# concentrador.net
KiCad netlist of a schematic drawn in Altium Designer
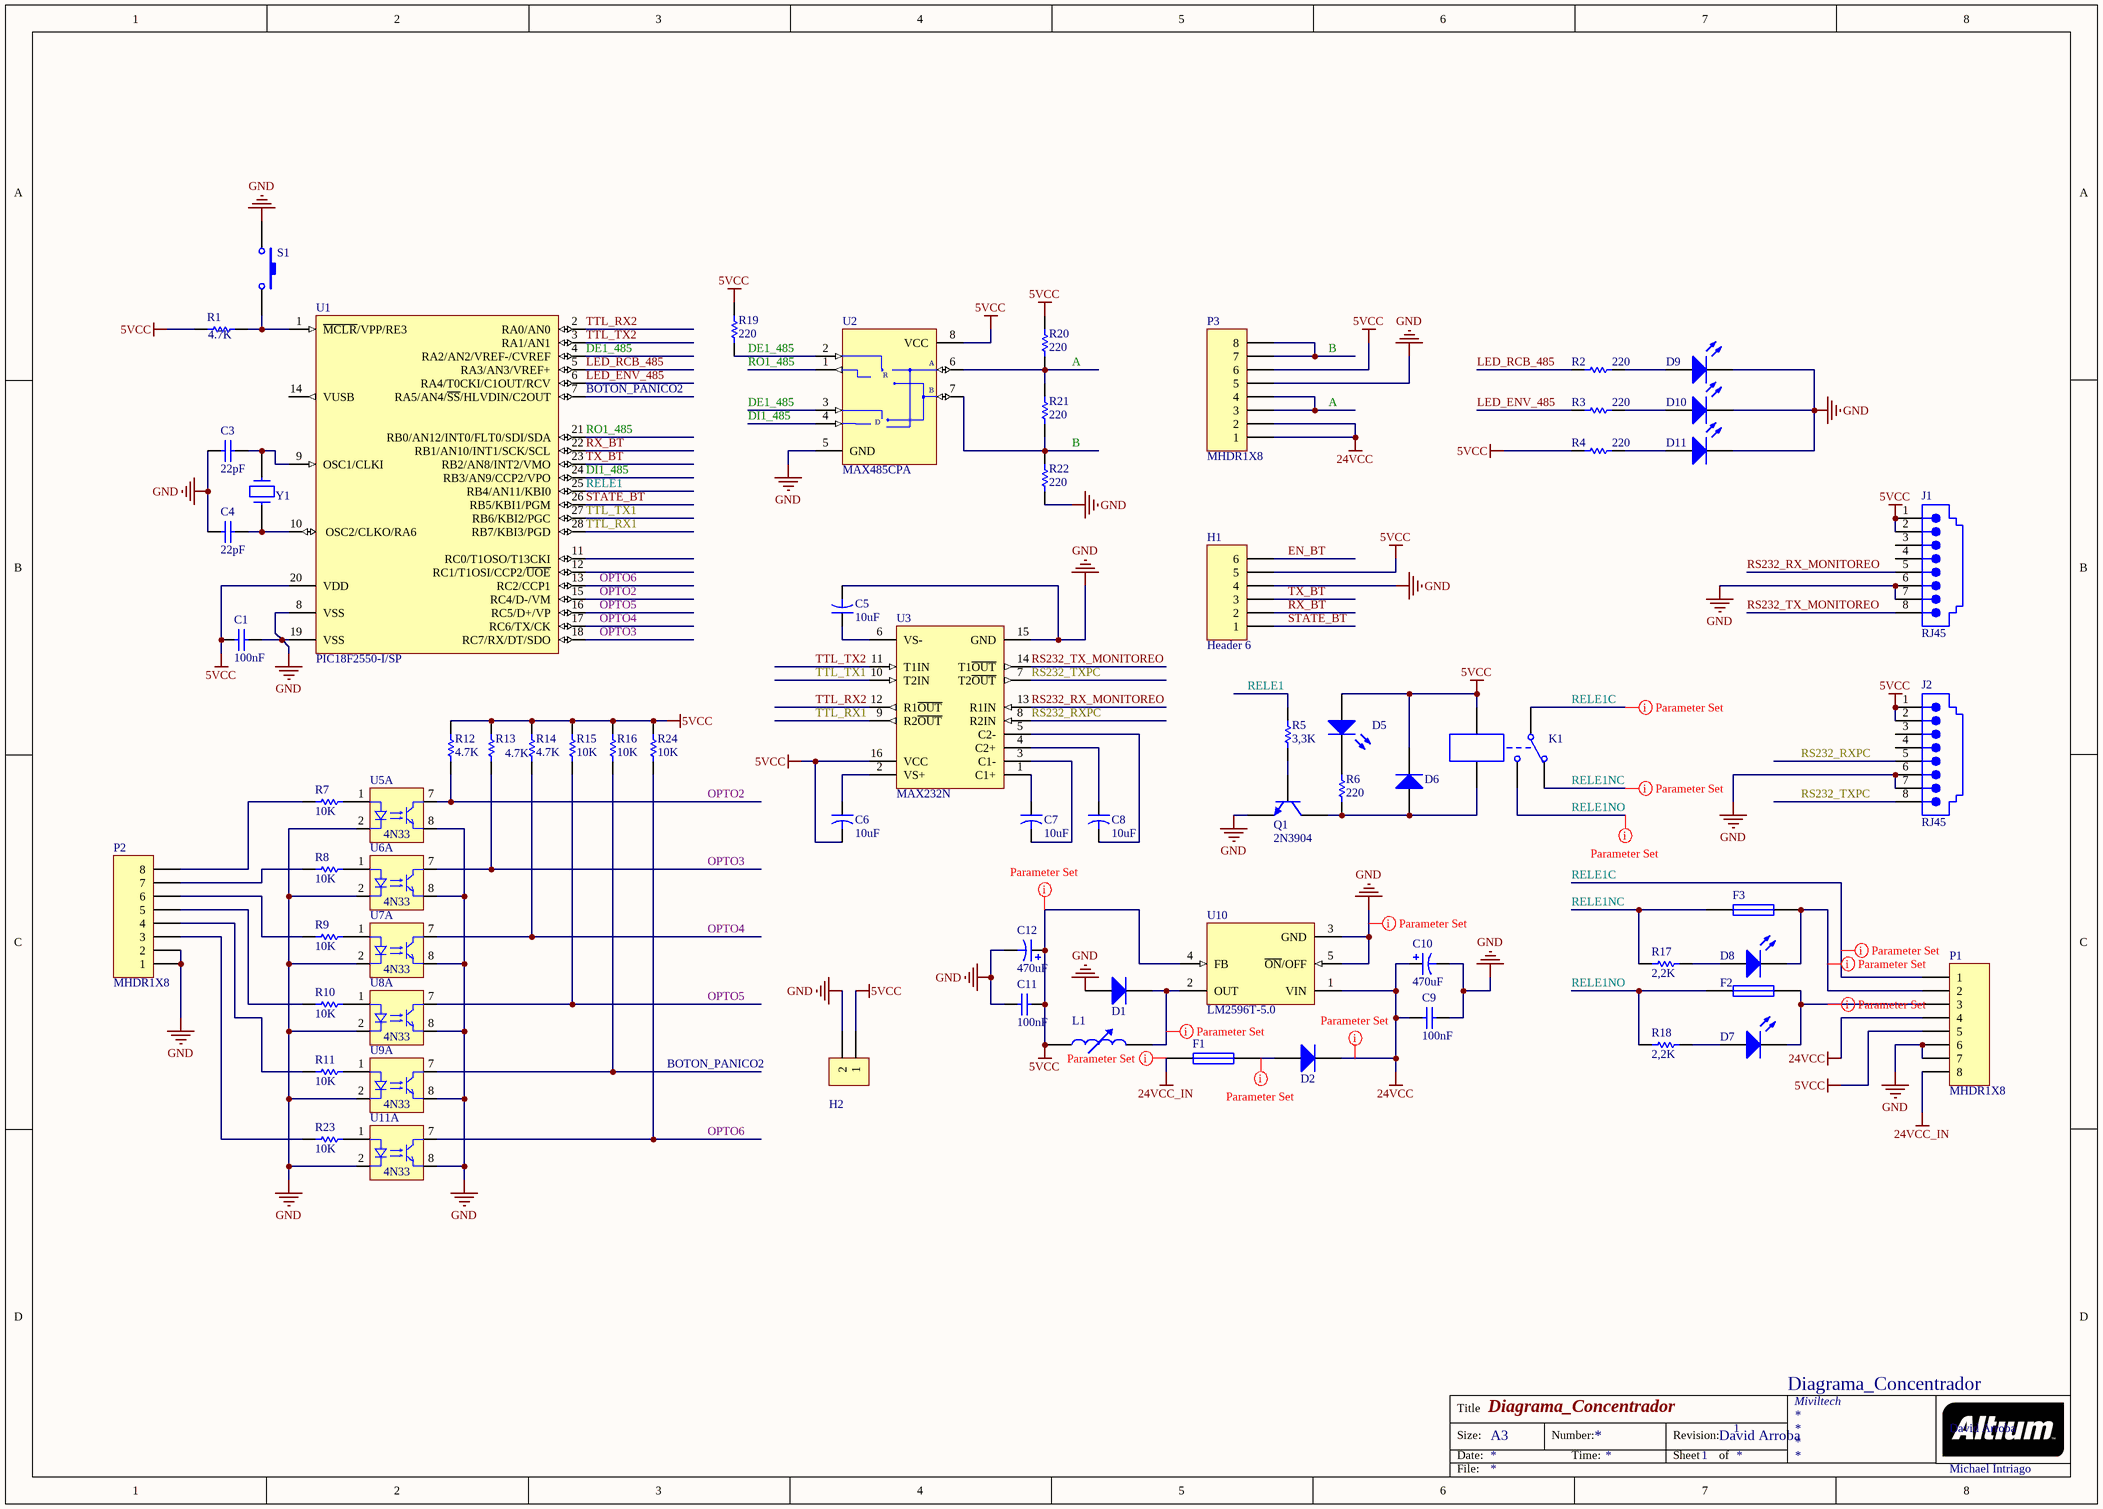
[diagram p0: concentrador.SchDoc]

(export (version "E")
  (design (tool "Eeschema 10.0.6"))
  (components
    (comp (ref "C1")
      (value "100nF")
      (footprint "VP44-2.5")
      (description "Dipped Radial Multilayer Ceramic Capacitor X7R: 220nF, 100V")
      (fields (field (name "Comment") "VP44BY224JB") (field (name "PUBLISHER") "Altium Limited"))
      (libsource (lib "Vishay Vitramon Ceramic Dipped Capacitor") (part "VP44BY224JB"))
    )
    (comp (ref "C3")
      (value "22pF")
      (footprint "VP31-2.5")
      (description "Dipped Radial Multilayer Ceramic Capacitor COG (NPO): 22pF, 100V")
      (fields (field (name "Comment") "VP31BA220JB") (field (name "PUBLISHER") "Altium Limited"))
      (libsource (lib "Vishay Vitramon Ceramic Dipped Capacitor") (part "VP31BA220JB"))
    )
    (comp (ref "C4")
      (value "22pF")
      (footprint "VP31-2.5")
      (description "Dipped Radial Multilayer Ceramic Capacitor COG (NPO): 22pF, 100V")
      (fields (field (name "Comment") "VP31BA220JB") (field (name "PUBLISHER") "Altium Limited"))
      (libsource (lib "Vishay Vitramon Ceramic Dipped Capacitor") (part "VP31BA220JB"))
    )
    (comp (ref "C5")
      (value "10uF")
      (footprint "C1UF")
      (description "Capacitor")
      (fields (field (name "Comment") "Cap2") (field (name "PUBLISHER") "Altium Limited"))
      (libsource (lib "Miscellaneous Devices") (part "Cap2"))
    )
    (comp (ref "C6")
      (value "10uF")
      (footprint "C1UF")
      (description "Capacitor")
      (fields (field (name "Comment") "Cap2") (field (name "PUBLISHER") "Altium Limited"))
      (libsource (lib "Miscellaneous Devices") (part "Cap2"))
    )
    (comp (ref "C7")
      (value "10uF")
      (footprint "C1UF")
      (description "Capacitor")
      (fields (field (name "Comment") "Cap2") (field (name "PUBLISHER") "Altium Limited"))
      (libsource (lib "Miscellaneous Devices") (part "Cap2"))
    )
    (comp (ref "C8")
      (value "10uF")
      (footprint "C1UF")
      (description "Capacitor")
      (fields (field (name "Comment") "Cap2") (field (name "PUBLISHER") "Altium Limited"))
      (libsource (lib "Miscellaneous Devices") (part "Cap2"))
    )
    (comp (ref "C9")
      (value "100nF")
      (footprint "VP44-2.5")
      (description "Dipped Radial Multilayer Ceramic Capacitor X7R: 220nF, 100V")
      (fields (field (name "Comment") "VP44BY224JB") (field (name "PUBLISHER") "Altium Limited"))
      (libsource (lib "Vishay Vitramon Ceramic Dipped Capacitor") (part "VP44BY224JB"))
    )
    (comp (ref "C10")
      (value "470uF")
      (footprint "C1000UF")
      (description "Polarized Capacitor (Radial)")
      (fields (field (name "Comment") "Cap Pol1") (field (name "PUBLISHER") "Altium Limited"))
      (libsource (lib "Miscellaneous Devices") (part "Cap Pol1"))
    )
    (comp (ref "C11")
      (value "100nF")
      (footprint "VP44-2.5")
      (description "Dipped Radial Multilayer Ceramic Capacitor X7R: 220nF, 100V")
      (fields (field (name "Comment") "VP44BY224JB") (field (name "PUBLISHER") "Altium Limited"))
      (libsource (lib "Vishay Vitramon Ceramic Dipped Capacitor") (part "VP44BY224JB"))
    )
    (comp (ref "C12")
      (value "470uF")
      (footprint "C1000UF")
      (description "Polarized Capacitor (Radial)")
      (fields (field (name "Comment") "Cap Pol1") (field (name "PUBLISHER") "Altium Limited"))
      (libsource (lib "Miscellaneous Devices") (part "Cap Pol1"))
    )
    (comp (ref "D1")
      (value "Diodo")
      (footprint "1N4000")
      (description "Diodo rectificador")
      (libsource (lib "Diodos") (part "Diodo"))
    )
    (comp (ref "D2")
      (value "Diodo")
      (footprint "1N4000")
      (description "Diodo rectificador")
      (libsource (lib "Diodos") (part "Diodo"))
    )
    (comp (ref "D5")
      (value "LED0")
      (footprint "LED3MM green")
      (description "Typical INFRARED GaAs LED")
      (fields (field (name "PUBLISHER") "Altium Limited"))
      (libsource (lib "Miscellaneous Devices") (part "LED0"))
    )
    (comp (ref "D6")
      (value "Diode 1N4001")
      (footprint "DIODE-0.3A")
      (description "1 Amp General Purpose Rectifier")
      (fields (field (name "PUBLISHER") "Altium Limited"))
      (libsource (lib "Miscellaneous Devices") (part "Diode 1N4001"))
    )
    (comp (ref "D7")
      (value "LED0")
      (footprint "LED3MM green")
      (description "Typical INFRARED GaAs LED")
      (fields (field (name "PUBLISHER") "Altium Limited"))
      (libsource (lib "Miscellaneous Devices") (part "LED0"))
    )
    (comp (ref "D8")
      (value "LED0")
      (footprint "LED3MM green")
      (description "Typical INFRARED GaAs LED")
      (fields (field (name "PUBLISHER") "Altium Limited"))
      (libsource (lib "Miscellaneous Devices") (part "LED0"))
    )
    (comp (ref "D9")
      (value "LED0")
      (footprint "LED3MM green")
      (description "Typical INFRARED GaAs LED")
      (fields (field (name "PUBLISHER") "Altium Limited"))
      (libsource (lib "Miscellaneous Devices") (part "LED0"))
    )
    (comp (ref "D10")
      (value "LED0")
      (footprint "LED3MM green")
      (description "Typical INFRARED GaAs LED")
      (fields (field (name "PUBLISHER") "Altium Limited"))
      (libsource (lib "Miscellaneous Devices") (part "LED0"))
    )
    (comp (ref "D11")
      (value "LED0")
      (footprint "LED3MM green")
      (description "Typical INFRARED GaAs LED")
      (fields (field (name "PUBLISHER") "Altium Limited"))
      (libsource (lib "Miscellaneous Devices") (part "LED0"))
    )
    (comp (ref "F1")
      (value "Fuse")
      (footprint "PORTA_FUSE")
      (fields (field (name "PUBLISHER") "Altium Limited"))
      (libsource (lib "Miscellaneous Devices") (part "Fuse 1"))
    )
    (comp (ref "F2")
      (value "Fuse")
      (footprint "PORTA_FUSE")
      (fields (field (name "PUBLISHER") "Altium Limited"))
      (libsource (lib "Miscellaneous Devices") (part "Fuse 1"))
    )
    (comp (ref "F3")
      (value "Fuse")
      (footprint "PORTA_FUSE")
      (fields (field (name "PUBLISHER") "Altium Limited"))
      (libsource (lib "Miscellaneous Devices") (part "Fuse 1"))
    )
    (comp (ref "H1")
      (value "Header 6")
      (footprint "Header 1X6")
      (description "Header, 6-Pin")
      (fields (field (name "PUBLISHER") "Altium Limited"))
      (libsource (lib "Conectores") (part "Header 6"))
    )
    (comp (ref "H2")
      (value "Header")
      (footprint "Header 1X2")
      (description "Header 2 pin")
      (libsource (lib "Conectores") (part "Header 2"))
    )
    (comp (ref "J1")
      (value "RJ45")
      (footprint "15-43-6233")
      (description "Right Angle, Standard Profile, RJ45-Keyed, Flange Mount PCB Jack")
      (fields (field (name "PUBLISHER") "Altium Limited"))
      (libsource (lib "Molex Modular Jack Right Angle") (part "15-43-6233"))
    )
    (comp (ref "J2")
      (value "RJ45")
      (footprint "15-43-6233")
      (description "Right Angle, Standard Profile, RJ45-Keyed, Flange Mount PCB Jack")
      (fields (field (name "PUBLISHER") "Altium Limited"))
      (libsource (lib "Molex Modular Jack Right Angle") (part "15-43-6233"))
    )
    (comp (ref "K1")
      (value "Relay-SPDT")
      (footprint "RELE")
      (description "Single-Pole Dual-Throw Relay")
      (fields (field (name "PUBLISHER") "Altium Limited"))
      (libsource (lib "Miscellaneous Devices") (part "Relay-SPDT"))
    )
    (comp (ref "L1")
      (value "Inductor Adj")
      (footprint "Inductor_redondo")
      (description "Adjustable Inductor")
      (fields (field (name "PUBLISHER") "Altium Limited"))
      (libsource (lib "Miscellaneous Devices") (part "Inductor Adj"))
    )
    (comp (ref "P1")
      (value "MHDR1X8")
      (footprint "8PEQ_TAIYUE_OK")
      (description "Header, 8-Pin")
      (fields (field (name "PUBLISHER") "Altium Limited"))
      (libsource (lib "") (part "MHDR1X8_1"))
    )
    (comp (ref "P2")
      (value "MHDR1X8")
      (footprint "8PEQ_TAIYUE_OK")
      (description "Header, 8-Pin")
      (fields (field (name "PUBLISHER") "Altium Limited"))
      (libsource (lib "Miscellaneous Connectors") (part "MHDR1X8"))
    )
    (comp (ref "P3")
      (value "MHDR1X8")
      (footprint "8PEQ_TAIYUE_OK")
      (description "Header, 8-Pin")
      (fields (field (name "PUBLISHER") "Altium Limited"))
      (libsource (lib "Miscellaneous Connectors") (part "MHDR1X8"))
    )
    (comp (ref "Q1")
      (value "2N3904")
      (footprint "2N3904_OK")
      (description "NPN General Purpose Amplifier")
      (fields (field (name "PUBLISHER") "Altium Limited"))
      (libsource (lib "Miscellaneous Devices") (part "2N3904"))
    )
    (comp (ref "R1")
      (value "4.7K")
      (footprint "AXIAL-0.3")
      (description "Resistor")
      (fields (field (name "Comment") "Res1") (field (name "PUBLISHER") "Altium Limited"))
      (libsource (lib "Miscellaneous Devices") (part "Res1"))
    )
    (comp (ref "R2")
      (value "220")
      (footprint "AXIAL-0.3")
      (description "Resistor")
      (fields (field (name "Comment") "Res1") (field (name "PUBLISHER") "Altium Limited"))
      (libsource (lib "Miscellaneous Devices") (part "Res1"))
    )
    (comp (ref "R3")
      (value "220")
      (footprint "AXIAL-0.3")
      (description "Resistor")
      (fields (field (name "Comment") "Res1") (field (name "PUBLISHER") "Altium Limited"))
      (libsource (lib "Miscellaneous Devices") (part "Res1"))
    )
    (comp (ref "R4")
      (value "220")
      (footprint "AXIAL-0.3")
      (description "Resistor")
      (fields (field (name "Comment") "Res1") (field (name "PUBLISHER") "Altium Limited"))
      (libsource (lib "Miscellaneous Devices") (part "Res1"))
    )
    (comp (ref "R5")
      (value "3,3K")
      (footprint "AXIAL-0.3")
      (description "Resistor")
      (fields (field (name "Comment") "Res1") (field (name "PUBLISHER") "Altium Limited"))
      (libsource (lib "Miscellaneous Devices") (part "Res1"))
    )
    (comp (ref "R6")
      (value "220")
      (footprint "AXIAL-0.3")
      (description "Resistor")
      (fields (field (name "Comment") "Res1") (field (name "PUBLISHER") "Altium Limited"))
      (libsource (lib "Miscellaneous Devices") (part "Res1"))
    )
    (comp (ref "R7")
      (value "10K")
      (footprint "AXIAL-0.3")
      (description "Resistor")
      (fields (field (name "Comment") "Res1") (field (name "PUBLISHER") "Altium Limited"))
      (libsource (lib "Miscellaneous Devices") (part "Res1"))
    )
    (comp (ref "R8")
      (value "10K")
      (footprint "AXIAL-0.3")
      (description "Resistor")
      (fields (field (name "Comment") "Res1") (field (name "PUBLISHER") "Altium Limited"))
      (libsource (lib "Miscellaneous Devices") (part "Res1"))
    )
    (comp (ref "R9")
      (value "10K")
      (footprint "AXIAL-0.3")
      (description "Resistor")
      (fields (field (name "Comment") "Res1") (field (name "PUBLISHER") "Altium Limited"))
      (libsource (lib "Miscellaneous Devices") (part "Res1"))
    )
    (comp (ref "R10")
      (value "10K")
      (footprint "AXIAL-0.3")
      (description "Resistor")
      (fields (field (name "Comment") "Res1") (field (name "PUBLISHER") "Altium Limited"))
      (libsource (lib "Miscellaneous Devices") (part "Res1"))
    )
    (comp (ref "R11")
      (value "10K")
      (footprint "AXIAL-0.3")
      (description "Resistor")
      (fields (field (name "Comment") "Res1") (field (name "PUBLISHER") "Altium Limited"))
      (libsource (lib "Miscellaneous Devices") (part "Res1"))
    )
    (comp (ref "R12")
      (value "4.7K")
      (footprint "AXIAL-0.3")
      (description "Resistor")
      (fields (field (name "Comment") "Res1") (field (name "PUBLISHER") "Altium Limited"))
      (libsource (lib "Miscellaneous Devices") (part "Res1"))
    )
    (comp (ref "R13")
      (value "4.7K")
      (footprint "AXIAL-0.3")
      (description "Resistor")
      (fields (field (name "Comment") "Res1") (field (name "PUBLISHER") "Altium Limited"))
      (libsource (lib "Miscellaneous Devices") (part "Res1"))
    )
    (comp (ref "R14")
      (value "4.7K")
      (footprint "AXIAL-0.3")
      (description "Resistor")
      (fields (field (name "Comment") "Res1") (field (name "PUBLISHER") "Altium Limited"))
      (libsource (lib "Miscellaneous Devices") (part "Res1"))
    )
    (comp (ref "R15")
      (value "10K")
      (footprint "AXIAL-0.3")
      (description "Resistor")
      (fields (field (name "Comment") "Res1") (field (name "PUBLISHER") "Altium Limited"))
      (libsource (lib "Miscellaneous Devices") (part "Res1"))
    )
    (comp (ref "R16")
      (value "10K")
      (footprint "AXIAL-0.3")
      (description "Resistor")
      (fields (field (name "Comment") "Res1") (field (name "PUBLISHER") "Altium Limited"))
      (libsource (lib "Miscellaneous Devices") (part "Res1"))
    )
    (comp (ref "R17")
      (value "2,2K")
      (footprint "AXIAL-0.3")
      (description "Resistor")
      (fields (field (name "Comment") "Res1") (field (name "PUBLISHER") "Altium Limited"))
      (libsource (lib "Miscellaneous Devices") (part "Res1"))
    )
    (comp (ref "R18")
      (value "2,2K")
      (footprint "AXIAL-0.3")
      (description "Resistor")
      (fields (field (name "Comment") "Res1") (field (name "PUBLISHER") "Altium Limited"))
      (libsource (lib "Miscellaneous Devices") (part "Res1"))
    )
    (comp (ref "R19")
      (value "220")
      (footprint "AXIAL-0.3")
      (description "Resistor")
      (fields (field (name "Comment") "Res1") (field (name "PUBLISHER") "Altium Limited"))
      (libsource (lib "Miscellaneous Devices") (part "Res1"))
    )
    (comp (ref "R20")
      (value "220")
      (footprint "AXIAL-0.3")
      (description "Resistor")
      (fields (field (name "Comment") "Res1") (field (name "PUBLISHER") "Altium Limited"))
      (libsource (lib "Miscellaneous Devices") (part "Res1"))
    )
    (comp (ref "R21")
      (value "220")
      (footprint "AXIAL-0.3")
      (description "Resistor")
      (fields (field (name "Comment") "Res1") (field (name "PUBLISHER") "Altium Limited"))
      (libsource (lib "Miscellaneous Devices") (part "Res1"))
    )
    (comp (ref "R22")
      (value "220")
      (footprint "AXIAL-0.3")
      (description "Resistor")
      (fields (field (name "Comment") "Res1") (field (name "PUBLISHER") "Altium Limited"))
      (libsource (lib "Miscellaneous Devices") (part "Res1"))
    )
    (comp (ref "R23")
      (value "10K")
      (footprint "AXIAL-0.3")
      (description "Resistor")
      (fields (field (name "Comment") "Res1") (field (name "PUBLISHER") "Altium Limited"))
      (libsource (lib "Miscellaneous Devices") (part "Res1"))
    )
    (comp (ref "R24")
      (value "10K")
      (footprint "AXIAL-0.3")
      (description "Resistor")
      (fields (field (name "Comment") "Res1") (field (name "PUBLISHER") "Altium Limited"))
      (libsource (lib "Miscellaneous Devices") (part "Res1"))
    )
    (comp (ref "S1")
      (value "Push Button")
      (footprint "PULSA4")
      (description "Switch")
      (fields (field (name "PUBLISHER") "Altium Limited"))
      (libsource (lib "Botones") (part "Push Button"))
    )
    (comp (ref "U1")
      (value "PIC18F2550-I/SP")
      (footprint "SPDIP300-SP28")
      (fields (field (name "PUBLISHER") "Altium Limited"))
      (libsource (lib "Microchip Microcontroller 8-Bit PIC18") (part "PIC18F2550-I/SP"))
    )
    (comp (ref "U2")
      (value "MAX485CPA")
      (footprint "PA8")
      (description "Low-Power, Slew-Rate-Limited RS-485/RS-422 Transceiver")
      (fields (field (name "PUBLISHER") "Altium Limited"))
      (libsource (lib "Maxim Communication Transceiver") (part "MAX485CPA"))
    )
    (comp (ref "U3")
      (value "MAX232N")
      (footprint "N016")
      (description "Dual EIA-232 Driver/Receiver")
      (fields (field (name "PUBLISHER") "Altium Limited"))
      (libsource (lib "TI Interface Line Transceiver") (part "MAX232N"))
    )
    (comp (ref "U5")
      (value "4N33")
      (footprint "4n35_4n33_6pines")
      (description "Optocoupler, Phototransistor Output, Dual Channel, TTL Compatible, Pb-free")
      (fields (field (name "PUBLISHER") "Altium Limited"))
      (libsource (lib "Vishay Optoelectronic Optocoupler") (part "ILD74"))
    )
    (comp (ref "U6")
      (value "4N33")
      (footprint "4n35_4n33_6pines")
      (description "Optocoupler, Phototransistor Output, Dual Channel, TTL Compatible, Pb-free")
      (fields (field (name "PUBLISHER") "Altium Limited"))
      (libsource (lib "Vishay Optoelectronic Optocoupler") (part "ILD74"))
    )
    (comp (ref "U7")
      (value "4N33")
      (footprint "4n35_4n33_6pines")
      (description "Optocoupler, Phototransistor Output, Dual Channel, TTL Compatible, Pb-free")
      (fields (field (name "PUBLISHER") "Altium Limited"))
      (libsource (lib "Vishay Optoelectronic Optocoupler") (part "ILD74"))
    )
    (comp (ref "U8")
      (value "4N33")
      (footprint "4n35_4n33_6pines")
      (description "Optocoupler, Phototransistor Output, Dual Channel, TTL Compatible, Pb-free")
      (fields (field (name "PUBLISHER") "Altium Limited"))
      (libsource (lib "Vishay Optoelectronic Optocoupler") (part "ILD74"))
    )
    (comp (ref "U9")
      (value "4N33")
      (footprint "4n35_4n33_6pines")
      (description "Optocoupler, Phototransistor Output, Dual Channel, TTL Compatible, Pb-free")
      (fields (field (name "PUBLISHER") "Altium Limited"))
      (libsource (lib "Vishay Optoelectronic Optocoupler") (part "ILD74"))
    )
    (comp (ref "U10")
      (value "LM2596T-5.0")
      (footprint "FP_LM2596_D_PCB")
      (description "SIMPLE SWITCHER Power Converter 150 KHz 3A Step-Down Voltage Regulator")
      (fields
        (field (name "MANUFACTURER") "National Semiconductor")
        (field (name "DIGIKEYPARTNUMBER") "LM2596T-5.0-ND")
        (field (name "PUBLISHER") "Altium Limited")
      )
      (libsource (lib "NSC Switcher") (part "LM2596T-5.0"))
    )
    (comp (ref "U11")
      (value "4N33")
      (footprint "4n35_4n33_6pines")
      (description "Optocoupler, Phototransistor Output, Dual Channel, TTL Compatible, Pb-free")
      (fields (field (name "PUBLISHER") "Altium Limited"))
      (libsource (lib "Vishay Optoelectronic Optocoupler") (part "ILD74"))
    )
    (comp (ref "Y1")
      (value "XTAL")
      (footprint "Cristal mini")
      (description "Cristal de cuarzo")
      (libsource (lib "Cristales de cuarzo") (part "Cristal de cuarzo"))
    )
  )
  (nets
    (net (code "1") (name "/A") (class "Default")
      (node (ref "P3") (pin "3") (pinfunction "3_3") (pintype "passive"))
      (node (ref "P3") (pin "4") (pinfunction "4_4") (pintype "passive"))
      (node (ref "R20") (pin "2") (pinfunction "2_2") (pintype "passive"))
      (node (ref "R21") (pin "1") (pinfunction "1_1") (pintype "passive"))
      (node (ref "U2") (pin "6") (pinfunction "A_6") (pintype "bidirectional"))
    )
    (net (code "2") (name "/B") (class "Default")
      (node (ref "P3") (pin "7") (pinfunction "7_7") (pintype "passive"))
      (node (ref "P3") (pin "8") (pinfunction "8_8") (pintype "passive"))
      (node (ref "R21") (pin "2") (pinfunction "2_2") (pintype "passive"))
      (node (ref "R22") (pin "1") (pinfunction "1_1") (pintype "passive"))
      (node (ref "U2") (pin "7") (pinfunction "B_7") (pintype "bidirectional"))
    )
    (net (code "3") (name "/BOTON_PANICO2") (class "Default")
      (node (ref "R16") (pin "2") (pinfunction "2_2") (pintype "passive"))
      (node (ref "U1") (pin "7") (pinfunction "RA5/AN4/~{SS}/HLVDIN/C2OUT_7") (pintype "bidirectional"))
      (node (ref "U9") (pin "7") (pinfunction "C_7") (pintype "passive"))
    )
    (net (code "4") (name "/DE1_485") (class "Default")
      (node (ref "R19") (pin "1") (pinfunction "1_1") (pintype "passive"))
      (node (ref "U1") (pin "4") (pinfunction "RA2/AN2/VREF-/CVREF_4") (pintype "bidirectional"))
      (node (ref "U2") (pin "2") (pinfunction "~{RE}_2") (pintype "input"))
      (node (ref "U2") (pin "3") (pinfunction "DE_3") (pintype "input"))
    )
    (net (code "5") (name "/DI1_485") (class "Default")
      (node (ref "U1") (pin "24") (pinfunction "RB3/AN9/CCP2/VPO_24") (pintype "bidirectional"))
      (node (ref "U2") (pin "4") (pinfunction "DI_4") (pintype "input"))
    )
    (net (code "6") (name "/EN_BT") (class "Default")
      (node (ref "H1") (pin "6") (pinfunction "6_6") (pintype "passive"))
    )
    (net (code "7") (name "/LED_ENV_485") (class "Default")
      (node (ref "R3") (pin "1") (pinfunction "1_1") (pintype "passive"))
      (node (ref "U1") (pin "6") (pinfunction "RA4/T0CKI/C1OUT/RCV_6") (pintype "bidirectional"))
    )
    (net (code "8") (name "/LED_RCB_485") (class "Default")
      (node (ref "R2") (pin "1") (pinfunction "1_1") (pintype "passive"))
      (node (ref "U1") (pin "5") (pinfunction "RA3/AN3/VREF+_5") (pintype "bidirectional"))
    )
    (net (code "9") (name "/OPTO2") (class "Default")
      (node (ref "R12") (pin "2") (pinfunction "2_2") (pintype "passive"))
      (node (ref "U1") (pin "15") (pinfunction "RC4/D-/VM_15") (pintype "bidirectional"))
      (node (ref "U5") (pin "7") (pinfunction "C_7") (pintype "passive"))
    )
    (net (code "10") (name "/OPTO3") (class "Default")
      (node (ref "R13") (pin "2") (pinfunction "2_2") (pintype "passive"))
      (node (ref "U1") (pin "18") (pinfunction "RC7/RX/DT/SDO_18") (pintype "bidirectional"))
      (node (ref "U6") (pin "7") (pinfunction "C_7") (pintype "passive"))
    )
    (net (code "11") (name "/OPTO4") (class "Default")
      (node (ref "R14") (pin "2") (pinfunction "2_2") (pintype "passive"))
      (node (ref "U1") (pin "17") (pinfunction "RC6/TX/CK_17") (pintype "bidirectional"))
      (node (ref "U7") (pin "7") (pinfunction "C_7") (pintype "passive"))
    )
    (net (code "12") (name "/OPTO5") (class "Default")
      (node (ref "R15") (pin "2") (pinfunction "2_2") (pintype "passive"))
      (node (ref "U1") (pin "16") (pinfunction "RC5/D+/VP_16") (pintype "bidirectional"))
      (node (ref "U8") (pin "7") (pinfunction "C_7") (pintype "passive"))
    )
    (net (code "13") (name "/OPTO6") (class "Default")
      (node (ref "R24") (pin "2") (pinfunction "2_2") (pintype "passive"))
      (node (ref "U1") (pin "13") (pinfunction "RC2/CCP1_13") (pintype "bidirectional"))
      (node (ref "U11") (pin "7") (pinfunction "C_7") (pintype "passive"))
    )
    (net (code "14") (name "/RELE1") (class "Default")
      (node (ref "R5") (pin "1") (pinfunction "1_1") (pintype "passive"))
      (node (ref "U1") (pin "25") (pinfunction "RB4/AN11/KBI0_25") (pintype "bidirectional"))
    )
    (net (code "15") (name "/RELE1C") (class "Default")
      (node (ref "K1") (pin "1") (pinfunction "1_1") (pintype "passive"))
      (node (ref "P1") (pin "1") (pinfunction "1_1") (pintype "passive"))
    )
    (net (code "16") (name "/RELE1NC") (class "Default")
      (node (ref "F3") (pin "1") (pinfunction "1_1") (pintype "passive"))
      (node (ref "K1") (pin "2") (pinfunction "2_2") (pintype "passive"))
      (node (ref "R17") (pin "1") (pinfunction "1_1") (pintype "passive"))
    )
    (net (code "17") (name "/RELE1NO") (class "Default")
      (node (ref "F2") (pin "1") (pinfunction "1_1") (pintype "passive"))
      (node (ref "K1") (pin "3") (pinfunction "3_3") (pintype "passive"))
      (node (ref "R18") (pin "1") (pinfunction "1_1") (pintype "passive"))
    )
    (net (code "18") (name "/RO1_485") (class "Default")
      (node (ref "U1") (pin "21") (pinfunction "RB0/AN12/INT0/FLT0/SDI/SDA_21") (pintype "bidirectional"))
      (node (ref "U2") (pin "1") (pinfunction "RO_1") (pintype "output"))
    )
    (net (code "19") (name "/RS232_RXPC") (class "Default")
      (node (ref "J2") (pin "5") (pinfunction "5_5") (pintype "passive"))
      (node (ref "U3") (pin "8") (pinfunction "R2IN_8") (pintype "input"))
    )
    (net (code "20") (name "/RS232_RX_MONITOREO") (class "Default")
      (node (ref "J1") (pin "5") (pinfunction "5_5") (pintype "passive"))
      (node (ref "U3") (pin "13") (pinfunction "R1IN_13") (pintype "input"))
    )
    (net (code "21") (name "/RS232_TXPC") (class "Default")
      (node (ref "J2") (pin "8") (pinfunction "8_8") (pintype "passive"))
      (node (ref "U3") (pin "7") (pinfunction "T2~{OUT}_7") (pintype "output"))
    )
    (net (code "22") (name "/RS232_TX_MONITOREO") (class "Default")
      (node (ref "J1") (pin "8") (pinfunction "8_8") (pintype "passive"))
      (node (ref "U3") (pin "14") (pinfunction "T1~{OUT}_14") (pintype "output"))
    )
    (net (code "23") (name "/RX_BT") (class "Default")
      (node (ref "H1") (pin "2") (pinfunction "2_2") (pintype "passive"))
      (node (ref "U1") (pin "22") (pinfunction "RB1/AN10/INT1/SCK/SCL_22") (pintype "bidirectional"))
    )
    (net (code "24") (name "/STATE_BT") (class "Default")
      (node (ref "H1") (pin "1") (pinfunction "1_1") (pintype "passive"))
      (node (ref "U1") (pin "26") (pinfunction "RB5/KBI1/PGM_26") (pintype "bidirectional"))
    )
    (net (code "25") (name "/TTL_RX1") (class "Default")
      (node (ref "U1") (pin "28") (pinfunction "RB7/KBI3/PGD_28") (pintype "bidirectional"))
      (node (ref "U3") (pin "9") (pinfunction "R2~{OUT}_9") (pintype "output"))
    )
    (net (code "26") (name "/TTL_RX2") (class "Default")
      (node (ref "U1") (pin "2") (pinfunction "RA0/AN0_2") (pintype "bidirectional"))
      (node (ref "U3") (pin "12") (pinfunction "R1~{OUT}_12") (pintype "output"))
    )
    (net (code "27") (name "/TTL_TX1") (class "Default")
      (node (ref "U1") (pin "27") (pinfunction "RB6/KBI2/PGC_27") (pintype "bidirectional"))
      (node (ref "U3") (pin "10") (pinfunction "T2IN_10") (pintype "input"))
    )
    (net (code "28") (name "/TTL_TX2") (class "Default")
      (node (ref "U1") (pin "3") (pinfunction "RA1/AN1_3") (pintype "bidirectional"))
      (node (ref "U3") (pin "11") (pinfunction "T1IN_11") (pintype "input"))
    )
    (net (code "29") (name "/TX_BT") (class "Default")
      (node (ref "H1") (pin "3") (pinfunction "3_3") (pintype "passive"))
      (node (ref "U1") (pin "23") (pinfunction "RB2/AN8/INT2/VMO_23") (pintype "bidirectional"))
    )
    (net (code "30") (name "5VCC") (class "Default")
      (node (ref "C1") (pin "1") (pinfunction "1_1") (pintype "passive"))
      (node (ref "C11") (pin "2") (pinfunction "2_2") (pintype "passive"))
      (node (ref "C12") (pin "1") (pinfunction "1_1") (pintype "passive"))
      (node (ref "C6") (pin "2") (pinfunction "2_2") (pintype "passive"))
      (node (ref "D5") (pin "1") (pinfunction "A_1") (pintype "passive"))
      (node (ref "D6") (pin "2") (pinfunction "K_2") (pintype "passive"))
      (node (ref "H1") (pin "5") (pinfunction "5_5") (pintype "passive"))
      (node (ref "H2") (pin "1") (pinfunction "1_1") (pintype "passive"))
      (node (ref "J1") (pin "1") (pinfunction "1_1") (pintype "passive"))
      (node (ref "J1") (pin "2") (pinfunction "2_2") (pintype "passive"))
      (node (ref "J2") (pin "1") (pinfunction "1_1") (pintype "passive"))
      (node (ref "J2") (pin "2") (pinfunction "2_2") (pintype "passive"))
      (node (ref "K1") (pin "4") (pinfunction "4_4") (pintype "passive"))
      (node (ref "L1") (pin "1") (pinfunction "1_1") (pintype "passive"))
      (node (ref "P1") (pin "5") (pinfunction "5_5") (pintype "passive"))
      (node (ref "P3") (pin "6") (pinfunction "6_6") (pintype "passive"))
      (node (ref "R1") (pin "1") (pinfunction "1_1") (pintype "passive"))
      (node (ref "R12") (pin "1") (pinfunction "1_1") (pintype "passive"))
      (node (ref "R13") (pin "1") (pinfunction "1_1") (pintype "passive"))
      (node (ref "R14") (pin "1") (pinfunction "1_1") (pintype "passive"))
      (node (ref "R15") (pin "1") (pinfunction "1_1") (pintype "passive"))
      (node (ref "R16") (pin "1") (pinfunction "1_1") (pintype "passive"))
      (node (ref "R19") (pin "2") (pinfunction "2_2") (pintype "passive"))
      (node (ref "R20") (pin "1") (pinfunction "1_1") (pintype "passive"))
      (node (ref "R24") (pin "1") (pinfunction "1_1") (pintype "passive"))
      (node (ref "R4") (pin "1") (pinfunction "1_1") (pintype "passive"))
      (node (ref "U1") (pin "20") (pinfunction "VDD_20") (pintype "power_in"))
      (node (ref "U10") (pin "4") (pinfunction "FB_4") (pintype "input"))
      (node (ref "U2") (pin "8") (pinfunction "VCC_8") (pintype "power_in"))
      (node (ref "U3") (pin "16") (pinfunction "VCC_16") (pintype "power_in"))
    )
    (net (code "31") (name "24VCC") (class "Default")
      (node (ref "C10") (pin "1") (pinfunction "1_1") (pintype "passive"))
      (node (ref "C9") (pin "1") (pinfunction "1_1") (pintype "passive"))
      (node (ref "D2") (pin "2") (pinfunction "K_2") (pintype "passive"))
      (node (ref "P1") (pin "4") (pinfunction "4_4") (pintype "passive"))
      (node (ref "P3") (pin "1") (pinfunction "1_1") (pintype "passive"))
      (node (ref "P3") (pin "2") (pinfunction "2_2") (pintype "passive"))
      (node (ref "U10") (pin "1") (pinfunction "VIN_1") (pintype "power_in"))
    )
    (net (code "32") (name "24VCC_IN") (class "Default")
      (node (ref "F1") (pin "2") (pinfunction "2_2") (pintype "passive"))
      (node (ref "P1") (pin "8") (pinfunction "8_8") (pintype "passive"))
    )
    (net (code "33") (name "GND") (class "Default")
      (node (ref "C1") (pin "2") (pinfunction "2_2") (pintype "passive"))
      (node (ref "C10") (pin "2") (pinfunction "2_2") (pintype "passive"))
      (node (ref "C11") (pin "1") (pinfunction "1_1") (pintype "passive"))
      (node (ref "C12") (pin "2") (pinfunction "2_2") (pintype "passive"))
      (node (ref "C3") (pin "2") (pinfunction "2_2") (pintype "passive"))
      (node (ref "C4") (pin "2") (pinfunction "2_2") (pintype "passive"))
      (node (ref "C5") (pin "2") (pinfunction "2_2") (pintype "passive"))
      (node (ref "C9") (pin "2") (pinfunction "2_2") (pintype "passive"))
      (node (ref "D1") (pin "1") (pinfunction "A_1") (pintype "passive"))
      (node (ref "D10") (pin "2") (pinfunction "K_2") (pintype "passive"))
      (node (ref "D11") (pin "2") (pinfunction "K_2") (pintype "passive"))
      (node (ref "D9") (pin "2") (pinfunction "K_2") (pintype "passive"))
      (node (ref "H1") (pin "4") (pinfunction "4_4") (pintype "passive"))
      (node (ref "H2") (pin "2") (pinfunction "2_2") (pintype "passive"))
      (node (ref "J1") (pin "6") (pinfunction "6_6") (pintype "passive"))
      (node (ref "J1") (pin "7") (pinfunction "7_7") (pintype "passive"))
      (node (ref "J2") (pin "6") (pinfunction "6_6") (pintype "passive"))
      (node (ref "J2") (pin "7") (pinfunction "7_7") (pintype "passive"))
      (node (ref "P1") (pin "6") (pinfunction "6_6") (pintype "passive"))
      (node (ref "P1") (pin "7") (pinfunction "7_7") (pintype "passive"))
      (node (ref "P2") (pin "1") (pinfunction "1_1") (pintype "passive"))
      (node (ref "P2") (pin "2") (pinfunction "2_2") (pintype "passive"))
      (node (ref "P3") (pin "5") (pinfunction "5_5") (pintype "passive"))
      (node (ref "Q1") (pin "1") (pinfunction "E_1") (pintype "passive"))
      (node (ref "R22") (pin "2") (pinfunction "2_2") (pintype "passive"))
      (node (ref "S1") (pin "1") (pinfunction "1_1") (pintype "passive"))
      (node (ref "U1") (pin "19") (pinfunction "VSS_19") (pintype "power_in"))
      (node (ref "U1") (pin "8") (pinfunction "VSS_8") (pintype "power_in"))
      (node (ref "U10") (pin "3") (pinfunction "GND_3") (pintype "power_in"))
      (node (ref "U10") (pin "5") (pinfunction "~{ON}/OFF_5") (pintype "input"))
      (node (ref "U11") (pin "2") (pinfunction "K_2") (pintype "passive"))
      (node (ref "U11") (pin "8") (pinfunction "E_8") (pintype "passive"))
      (node (ref "U2") (pin "5") (pinfunction "GND_5") (pintype "power_in"))
      (node (ref "U3") (pin "15") (pinfunction "GND_15") (pintype "power_in"))
      (node (ref "U5") (pin "2") (pinfunction "K_2") (pintype "passive"))
      (node (ref "U5") (pin "8") (pinfunction "E_8") (pintype "passive"))
      (node (ref "U6") (pin "2") (pinfunction "K_2") (pintype "passive"))
      (node (ref "U6") (pin "8") (pinfunction "E_8") (pintype "passive"))
      (node (ref "U7") (pin "2") (pinfunction "K_2") (pintype "passive"))
      (node (ref "U7") (pin "8") (pinfunction "E_8") (pintype "passive"))
      (node (ref "U8") (pin "2") (pinfunction "K_2") (pintype "passive"))
      (node (ref "U8") (pin "8") (pinfunction "E_8") (pintype "passive"))
      (node (ref "U9") (pin "2") (pinfunction "K_2") (pintype "passive"))
      (node (ref "U9") (pin "8") (pinfunction "E_8") (pintype "passive"))
    )
    (net (code "34") (name "Net-(D1-K)") (class "Default")
      (node (ref "D1") (pin "2") (pinfunction "K_2") (pintype "passive"))
      (node (ref "L1") (pin "2") (pinfunction "2_2") (pintype "passive"))
      (node (ref "U10") (pin "2") (pinfunction "OUT_2") (pintype "power_in"))
    )
    (net (code "35") (name "Net-(D2-A)") (class "Default")
      (node (ref "D2") (pin "1") (pinfunction "A_1") (pintype "passive"))
      (node (ref "F1") (pin "1") (pinfunction "1_1") (pintype "passive"))
    )
    (net (code "36") (name "Net-(D5-K)") (class "Default")
      (node (ref "D5") (pin "2") (pinfunction "K_2") (pintype "passive"))
      (node (ref "R6") (pin "2") (pinfunction "2_2") (pintype "passive"))
    )
    (net (code "37") (name "Net-(D6-A)") (class "Default")
      (node (ref "D6") (pin "1") (pinfunction "A_1") (pintype "passive"))
      (node (ref "K1") (pin "5") (pinfunction "5_5") (pintype "passive"))
      (node (ref "Q1") (pin "3") (pinfunction "C_3") (pintype "passive"))
      (node (ref "R6") (pin "1") (pinfunction "1_1") (pintype "passive"))
    )
    (net (code "38") (name "Net-(D7-A)") (class "Default")
      (node (ref "D7") (pin "1") (pinfunction "A_1") (pintype "passive"))
      (node (ref "R18") (pin "2") (pinfunction "2_2") (pintype "passive"))
    )
    (net (code "39") (name "Net-(D7-K)") (class "Default")
      (node (ref "D7") (pin "2") (pinfunction "K_2") (pintype "passive"))
      (node (ref "F2") (pin "2") (pinfunction "2_2") (pintype "passive"))
      (node (ref "P1") (pin "3") (pinfunction "3_3") (pintype "passive"))
    )
    (net (code "40") (name "Net-(D8-A)") (class "Default")
      (node (ref "D8") (pin "1") (pinfunction "A_1") (pintype "passive"))
      (node (ref "R17") (pin "2") (pinfunction "2_2") (pintype "passive"))
    )
    (net (code "41") (name "Net-(D8-K)") (class "Default")
      (node (ref "D8") (pin "2") (pinfunction "K_2") (pintype "passive"))
      (node (ref "F3") (pin "2") (pinfunction "2_2") (pintype "passive"))
      (node (ref "P1") (pin "2") (pinfunction "2_2") (pintype "passive"))
    )
    (net (code "42") (name "Net-(D9-A)") (class "Default")
      (node (ref "D9") (pin "1") (pinfunction "A_1") (pintype "passive"))
      (node (ref "R2") (pin "2") (pinfunction "2_2") (pintype "passive"))
    )
    (net (code "43") (name "Net-(D10-A)") (class "Default")
      (node (ref "D10") (pin "1") (pinfunction "A_1") (pintype "passive"))
      (node (ref "R3") (pin "2") (pinfunction "2_2") (pintype "passive"))
    )
    (net (code "44") (name "Net-(D11-A)") (class "Default")
      (node (ref "D11") (pin "1") (pinfunction "A_1") (pintype "passive"))
      (node (ref "R4") (pin "2") (pinfunction "2_2") (pintype "passive"))
    )
    (net (code "45") (name "Net-(P2-Pad3)") (class "Default")
      (node (ref "P2") (pin "3") (pinfunction "3_3") (pintype "passive"))
      (node (ref "R23") (pin "2") (pinfunction "2_2") (pintype "passive"))
    )
    (net (code "46") (name "Net-(P2-Pad4)") (class "Default")
      (node (ref "P2") (pin "4") (pinfunction "4_4") (pintype "passive"))
      (node (ref "R11") (pin "2") (pinfunction "2_2") (pintype "passive"))
    )
    (net (code "47") (name "Net-(P2-Pad5)") (class "Default")
      (node (ref "P2") (pin "5") (pinfunction "5_5") (pintype "passive"))
      (node (ref "R10") (pin "2") (pinfunction "2_2") (pintype "passive"))
    )
    (net (code "48") (name "Net-(P2-Pad6)") (class "Default")
      (node (ref "P2") (pin "6") (pinfunction "6_6") (pintype "passive"))
      (node (ref "R9") (pin "2") (pinfunction "2_2") (pintype "passive"))
    )
    (net (code "49") (name "Net-(P2-Pad7)") (class "Default")
      (node (ref "P2") (pin "7") (pinfunction "7_7") (pintype "passive"))
      (node (ref "R8") (pin "2") (pinfunction "2_2") (pintype "passive"))
    )
    (net (code "50") (name "Net-(P2-Pad8)") (class "Default")
      (node (ref "P2") (pin "8") (pinfunction "8_8") (pintype "passive"))
      (node (ref "R7") (pin "2") (pinfunction "2_2") (pintype "passive"))
    )
    (net (code "51") (name "Net-(Q1-B)") (class "Default")
      (node (ref "Q1") (pin "2") (pinfunction "B_2") (pintype "passive"))
      (node (ref "R5") (pin "2") (pinfunction "2_2") (pintype "passive"))
    )
    (net (code "52") (name "Net-(U1-OSC1{slash}CLKI)") (class "Default")
      (node (ref "C3") (pin "1") (pinfunction "1_1") (pintype "passive"))
      (node (ref "U1") (pin "9") (pinfunction "OSC1/CLKI_9") (pintype "input"))
      (node (ref "Y1") (pin "2") (pinfunction "2_2") (pintype "passive"))
    )
    (net (code "53") (name "Net-(U1-OSC2{slash}CLKO{slash}RA6)") (class "Default")
      (node (ref "C4") (pin "1") (pinfunction "1_1") (pintype "passive"))
      (node (ref "U1") (pin "10") (pinfunction "OSC2/CLKO/RA6_10") (pintype "bidirectional"))
      (node (ref "Y1") (pin "1") (pinfunction "1_1") (pintype "passive"))
    )
    (net (code "54") (name "Net-(U1-~{MCLR}{slash}VPP{slash}RE3)") (class "Default")
      (node (ref "R1") (pin "2") (pinfunction "2_2") (pintype "passive"))
      (node (ref "S1") (pin "2") (pinfunction "2_2") (pintype "passive"))
      (node (ref "U1") (pin "1") (pinfunction "~{MCLR}/VPP/RE3_1") (pintype "input"))
    )
    (net (code "55") (name "Net-(U3-C1+)") (class "Default")
      (node (ref "C7") (pin "1") (pinfunction "1_1") (pintype "passive"))
      (node (ref "U3") (pin "1") (pinfunction "C1+_1") (pintype "passive"))
    )
    (net (code "56") (name "Net-(U3-C1-)") (class "Default")
      (node (ref "C7") (pin "2") (pinfunction "2_2") (pintype "passive"))
      (node (ref "U3") (pin "3") (pinfunction "C1-_3") (pintype "passive"))
    )
    (net (code "57") (name "Net-(U3-C2+)") (class "Default")
      (node (ref "C8") (pin "1") (pinfunction "1_1") (pintype "passive"))
      (node (ref "U3") (pin "4") (pinfunction "C2+_4") (pintype "passive"))
    )
    (net (code "58") (name "Net-(U3-C2-)") (class "Default")
      (node (ref "C8") (pin "2") (pinfunction "2_2") (pintype "passive"))
      (node (ref "U3") (pin "5") (pinfunction "C2-_5") (pintype "passive"))
    )
    (net (code "59") (name "Net-(U3-VS+)") (class "Default")
      (node (ref "C6") (pin "1") (pinfunction "1_1") (pintype "passive"))
      (node (ref "U3") (pin "2") (pinfunction "VS+_2") (pintype "power_in"))
    )
    (net (code "60") (name "Net-(U3-VS-)") (class "Default")
      (node (ref "C5") (pin "1") (pinfunction "1_1") (pintype "passive"))
      (node (ref "U3") (pin "6") (pinfunction "VS-_6") (pintype "power_in"))
    )
    (net (code "61") (name "Net-(U5A-A)") (class "Default")
      (node (ref "R7") (pin "1") (pinfunction "1_1") (pintype "passive"))
      (node (ref "U5") (pin "1") (pinfunction "A_1") (pintype "passive"))
    )
    (net (code "62") (name "Net-(U6A-A)") (class "Default")
      (node (ref "R8") (pin "1") (pinfunction "1_1") (pintype "passive"))
      (node (ref "U6") (pin "1") (pinfunction "A_1") (pintype "passive"))
    )
    (net (code "63") (name "Net-(U7A-A)") (class "Default")
      (node (ref "R9") (pin "1") (pinfunction "1_1") (pintype "passive"))
      (node (ref "U7") (pin "1") (pinfunction "A_1") (pintype "passive"))
    )
    (net (code "64") (name "Net-(U8A-A)") (class "Default")
      (node (ref "R10") (pin "1") (pinfunction "1_1") (pintype "passive"))
      (node (ref "U8") (pin "1") (pinfunction "A_1") (pintype "passive"))
    )
    (net (code "65") (name "Net-(U9A-A)") (class "Default")
      (node (ref "R11") (pin "1") (pinfunction "1_1") (pintype "passive"))
      (node (ref "U9") (pin "1") (pinfunction "A_1") (pintype "passive"))
    )
    (net (code "66") (name "Net-(U11A-A)") (class "Default")
      (node (ref "R23") (pin "1") (pinfunction "1_1") (pintype "passive"))
      (node (ref "U11") (pin "1") (pinfunction "A_1") (pintype "passive"))
    )
    (net (code "67") (name "unconnected-(J1-Pad3)") (class "Default")
      (node (ref "J1") (pin "3") (pinfunction "3_3") (pintype "passive"))
    )
    (net (code "68") (name "unconnected-(J1-Pad4)") (class "Default")
      (node (ref "J1") (pin "4") (pinfunction "4_4") (pintype "passive"))
    )
    (net (code "69") (name "unconnected-(J2-Pad3)") (class "Default")
      (node (ref "J2") (pin "3") (pinfunction "3_3") (pintype "passive"))
    )
    (net (code "70") (name "unconnected-(J2-Pad4)") (class "Default")
      (node (ref "J2") (pin "4") (pinfunction "4_4") (pintype "passive"))
    )
    (net (code "71") (name "unconnected-(U1-RC0{slash}T1OSO{slash}T13CKI-Pad11)") (class "Default")
      (node (ref "U1") (pin "11") (pinfunction "RC0/T1OSO/T13CKI_11") (pintype "bidirectional"))
    )
    (net (code "72") (name "unconnected-(U1-RC1{slash}T1OSI{slash}CCP2{slash}~{UOE}-Pad12)") (class "Default")
      (node (ref "U1") (pin "12") (pinfunction "RC1/T1OSI/CCP2/~{UOE}_12") (pintype "bidirectional"))
    )
    (net (code "73") (name "unconnected-(U1-VUSB-Pad14)") (class "Default")
      (node (ref "U1") (pin "14") (pinfunction "VUSB_14") (pintype "output"))
    )
  )
)
